# USB_PD_POWER.net
KiCad netlist of a schematic drawn in Altium Designer
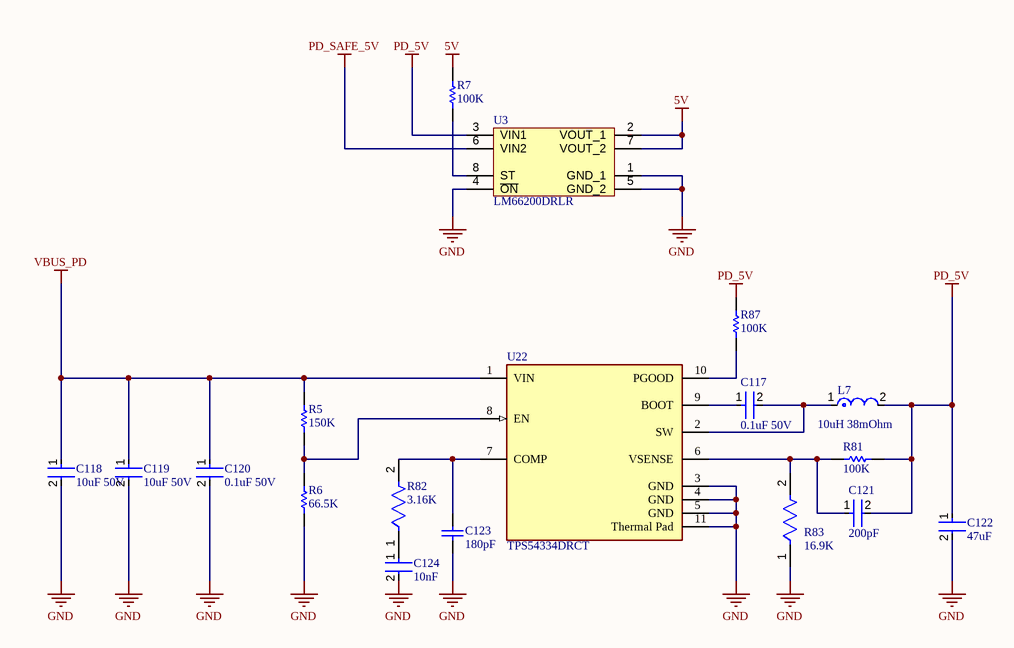
[diagram p0: USB_PD_POWER.SchDoc]

(export (version "E")
  (design (tool "Eeschema 10.0.6"))
  (components
    (comp (ref "C117")
      (value "0.1uF 50V")
      (footprint "FP-C0805C-DN-MFG")
      (description "CAP CER 0.1UF 50V X7R 0805")
      (fields (field (name "TOLERANCE") "0.2") (field (name "MANUFACTURER PART NUMBER") "C0805C104M5RACTU"))
      (libsource (lib "Altium Content Vault") (part "b4654b650e69147ec39a6b967a45e02"))
    )
    (comp (ref "C118")
      (value "10uF 50V")
      (footprint "FP-C3225-250-0_4-MFG")
      (description "Multilayer Ceramic Capacitors 10uF ±20% 50V X7R SMD 1210")
      (fields (field (name "TOLERANCE") "20%"))
      (libsource (lib "Altium Content Vault") (part "02cd4be3c70576c341d710602a673aa"))
    )
    (comp (ref "C119")
      (value "10uF 50V")
      (footprint "FP-C3225-250-0_4-MFG")
      (description "Multilayer Ceramic Capacitors 10uF ±20% 50V X7R SMD 1210")
      (fields (field (name "TOLERANCE") "20%"))
      (libsource (lib "Altium Content Vault") (part "02cd4be3c70576c341d710602a673aa"))
    )
    (comp (ref "C120")
      (value "0.1uF 50V")
      (footprint "FP-C0805C-DN-MFG")
      (description "CAP CER 0.1UF 50V X7R 0805")
      (fields (field (name "TOLERANCE") "0.2") (field (name "MANUFACTURER PART NUMBER") "C0805C104M5RACTU"))
      (libsource (lib "Altium Content Vault") (part "b4654b650e69147ec39a6b967a45e02"))
    )
    (comp (ref "C121")
      (value "200pF")
      (footprint "FP-C0402-BB-MFG")
      (description "CAP CER 200PF 50V NP0 0402")
      (fields
        (field (name "MANUFACTURER PART NUMBER") "C0402C201J5GACTU")
        (field (name "OCTOPART") "https://octopart.com/c0402c201j5gactu-kemet-19049754")
      )
      (libsource (lib "Altium Content Vault") (part "b4654b650e69147ec39a6b967a45e02"))
    )
    (comp (ref "C122")
      (value "47uF")
      (footprint "FP-C3216-160-0_2-IPC_C")
      (description "Multilayer Ceramic Capacitors 47uF ±20% 10V X6S SMD 1206")
      (fields (field (name "TOLERANCE") "20%"))
      (libsource (lib "Altium Content Vault") (part "11868f565c42a9108669ba33697ecf6"))
    )
    (comp (ref "C123")
      (value "180pF")
      (footprint "CAPC1005X55X25NL05T10")
      (fields (field (name "MANUFACTURER") "Murata") (field (name "PART NUMBER") "GRM1555C1H181JA01D"))
      (libsource (lib "Altium Content Vault") (part "CAP"))
    )
    (comp (ref "C124")
      (value "10nF")
      (footprint "FP-GRM155-0_05-IPC_C")
      (description "Chip Multilayer Ceramic Capacitors for General Purpose, 0402, 10000pF, X7R, 15%, 10%, 50V")
      (fields (field (name "TOLERANCE") "10%") (field (name "VOLTAGE") "25V"))
      (libsource (lib "Altium Content Vault") (part "02cd4be3c70576c341d710602a673aa"))
    )
    (comp (ref "L7")
      (value "10uH 38mOhm")
      (footprint "FP-XAL5050-MFG")
      (description "Power Inductors - SMD 8.2uH Shld 20% 6.1A 34.95mOhms AECQ2")
      (fields (field (name "TOLERANCE") "20%"))
      (libsource (lib "Altium Content Vault") (part "4cc4b267dca4c8e51f7102f422741d8"))
    )
    (comp (ref "R5")
      (value "150K")
      (footprint "RESC1005X40X25NL10T10")
      (fields
        (field (name "PART NUMBER") "CRG0402F150K")
        (field (name "MANUFACTURER") "TE Connectivity / AMP")
      )
      (libsource (lib "Altium Content Vault") (part "RES"))
    )
    (comp (ref "R6")
      (value "66.5K")
      (footprint "RESC1005X40X25ML05T05")
      (fields (field (name "PART NUMBER") "CRCW040266K5FKED") (field (name "MANUFACTURER") "Vishay Dale"))
      (libsource (lib "Altium Content Vault") (part "RES"))
    )
    (comp (ref "R7")
      (value "100K")
      (footprint "RESC1005X40X25NL05T10")
      (fields (field (name "PART NUMBER") "RC0402FR-07100KL") (field (name "MANUFACTURER") "Yageo / Phycomp"))
      (libsource (lib "Altium Content Vault") (part "RES"))
    )
    (comp (ref "R81")
      (value "100K")
      (footprint "RESC1005X40X25NL05T10")
      (fields (field (name "PART NUMBER") "RC0402FR-07100KL") (field (name "MANUFACTURER") "Yageo / Phycomp"))
      (libsource (lib "Altium Content Vault") (part "RES"))
    )
    (comp (ref "R82")
      (value "3.16K")
      (footprint "FP-CRCW0402-e3-IPC_C")
      (description "RES Thick Film, 3.16kΩ, 1%, 0.063W, 100ppm/°C, 0402")
      (libsource (lib "Altium Content Vault") (part "1029c3af85768c4190bb7ad29bc67b5"))
    )
    (comp (ref "R83")
      (value "16.9K")
      (footprint "FP-CRCW0402-e3-MFG")
      (description "RES Thick Film, 16.9kΩ, 1%, 0.063W, 100ppm/°C, 0402")
      (fields (field (name "TOLERANCE") "1%"))
      (libsource (lib "Altium Content Vault") (part "1029c3af85768c4190bb7ad29bc67b5"))
    )
    (comp (ref "R87")
      (value "100K")
      (footprint "RESC1005X40X25NL05T10")
      (fields (field (name "PART NUMBER") "RC0402FR-07100KL") (field (name "MANUFACTURER") "Yageo / Phycomp"))
      (libsource (lib "Altium Content Vault") (part "RES"))
    )
    (comp (ref "U3")
      (value "LM66200DRLR")
      (footprint "SamacSys:SOTFL50P160X60-8N")
      (description "Integrated Circuit")
      (fields (field (name "MOUSER PART NUMBER") "595-LM66200DRLR"))
      (libsource (lib "SamacSys") (part "LM66200DRLR"))
    )
    (comp (ref "U22")
      (value "TPS54334DRCT")
      (footprint "FP-DRC0010J-IPC_B")
      (description "IC REG BUCK ADJUSTABLE 3A 10VSON")
      (libsource (lib "Altium Content Vault") (part "4a854411a5b3307c0f21c01bb8057e0"))
    )
  )
  (nets
    (net (code "1") (name "5V") (class "Default")
      (node (ref "R7") (pin "1") (pinfunction "1_1") (pintype "passive"))
      (node (ref "U3") (pin "2") (pinfunction "VOUT_1_2") (pintype "passive"))
      (node (ref "U3") (pin "7") (pinfunction "VOUT_2_7") (pintype "passive"))
    )
    (net (code "2") (name "GND") (class "Default")
      (node (ref "C118") (pin "2") (pinfunction "2_2") (pintype "passive"))
      (node (ref "C119") (pin "2") (pinfunction "2_2") (pintype "passive"))
      (node (ref "C120") (pin "2") (pinfunction "2_2") (pintype "passive"))
      (node (ref "C122") (pin "2") (pinfunction "2_2") (pintype "passive"))
      (node (ref "C123") (pin "1") (pinfunction "1_1") (pintype "passive"))
      (node (ref "C124") (pin "2") (pinfunction "2_2") (pintype "passive"))
      (node (ref "R6") (pin "1") (pinfunction "1_1") (pintype "passive"))
      (node (ref "R83") (pin "1") (pinfunction "1_1") (pintype "passive"))
      (node (ref "U22") (pin "11") (pinfunction "Thermal_Pad_11") (pintype "power_in"))
      (node (ref "U22") (pin "3") (pinfunction "GND_3") (pintype "power_in"))
      (node (ref "U22") (pin "4") (pinfunction "GND_4") (pintype "power_in"))
      (node (ref "U22") (pin "5") (pinfunction "GND_5") (pintype "power_in"))
      (node (ref "U3") (pin "1") (pinfunction "GND_1_1") (pintype "passive"))
      (node (ref "U3") (pin "4") (pinfunction "~{ON}_4") (pintype "passive"))
      (node (ref "U3") (pin "5") (pinfunction "GND_2_5") (pintype "passive"))
    )
    (net (code "3") (name "Net-(C124-Pad1)") (class "Default")
      (node (ref "C124") (pin "1") (pinfunction "1_1") (pintype "passive"))
      (node (ref "R82") (pin "1") (pinfunction "1_1") (pintype "passive"))
    )
    (net (code "4") (name "Net-(U3-ST)") (class "Default")
      (node (ref "R7") (pin "2") (pinfunction "2_2") (pintype "passive"))
      (node (ref "U3") (pin "8") (pinfunction "ST_8") (pintype "passive"))
    )
    (net (code "5") (name "Net-(U22-BOOT)") (class "Default")
      (node (ref "C117") (pin "1") (pinfunction "1_1") (pintype "passive"))
      (node (ref "U22") (pin "9") (pinfunction "BOOT_9") (pintype "passive"))
    )
    (net (code "6") (name "Net-(U22-COMP)") (class "Default")
      (node (ref "C123") (pin "2") (pinfunction "2_2") (pintype "passive"))
      (node (ref "R82") (pin "2") (pinfunction "2_2") (pintype "passive"))
      (node (ref "U22") (pin "7") (pinfunction "COMP_7") (pintype "passive"))
    )
    (net (code "7") (name "Net-(U22-EN)") (class "Default")
      (node (ref "R5") (pin "1") (pinfunction "1_1") (pintype "passive"))
      (node (ref "R6") (pin "2") (pinfunction "2_2") (pintype "passive"))
      (node (ref "U22") (pin "8") (pinfunction "EN_8") (pintype "input"))
    )
    (net (code "8") (name "Net-(U22-PGOOD)") (class "Default")
      (node (ref "R87") (pin "2") (pinfunction "2_2") (pintype "passive"))
      (node (ref "U22") (pin "10") (pinfunction "PGOOD_10") (pintype "passive"))
    )
    (net (code "9") (name "Net-(U22-SW)") (class "Default")
      (node (ref "C117") (pin "2") (pinfunction "2_2") (pintype "passive"))
      (node (ref "L7") (pin "1") (pinfunction "1_1") (pintype "passive"))
      (node (ref "U22") (pin "2") (pinfunction "SW_2") (pintype "passive"))
    )
    (net (code "10") (name "Net-(U22-VSENSE)") (class "Default")
      (node (ref "C121") (pin "1") (pinfunction "1_1") (pintype "passive"))
      (node (ref "R81") (pin "2") (pinfunction "2_2") (pintype "passive"))
      (node (ref "R83") (pin "2") (pinfunction "2_2") (pintype "passive"))
      (node (ref "U22") (pin "6") (pinfunction "VSENSE_6") (pintype "passive"))
    )
    (net (code "11") (name "PD_5V") (class "Default")
      (node (ref "C121") (pin "2") (pinfunction "2_2") (pintype "passive"))
      (node (ref "C122") (pin "1") (pinfunction "1_1") (pintype "passive"))
      (node (ref "L7") (pin "2") (pinfunction "2_2") (pintype "passive"))
      (node (ref "R81") (pin "1") (pinfunction "1_1") (pintype "passive"))
      (node (ref "R87") (pin "1") (pinfunction "1_1") (pintype "passive"))
      (node (ref "U3") (pin "3") (pinfunction "VIN1_3") (pintype "passive"))
    )
    (net (code "12") (name "PD_SAFE_5V") (class "Default")
      (node (ref "U3") (pin "6") (pinfunction "VIN2_6") (pintype "passive"))
    )
    (net (code "13") (name "VBUS_PD") (class "Default")
      (node (ref "C118") (pin "1") (pinfunction "1_1") (pintype "passive"))
      (node (ref "C119") (pin "1") (pinfunction "1_1") (pintype "passive"))
      (node (ref "C120") (pin "1") (pinfunction "1_1") (pintype "passive"))
      (node (ref "R5") (pin "2") (pinfunction "2_2") (pintype "passive"))
      (node (ref "U22") (pin "1") (pinfunction "VIN_1") (pintype "power_in"))
    )
  )
)
